# amp_test_4.net
KiCad netlist of a schematic drawn in EAGLE
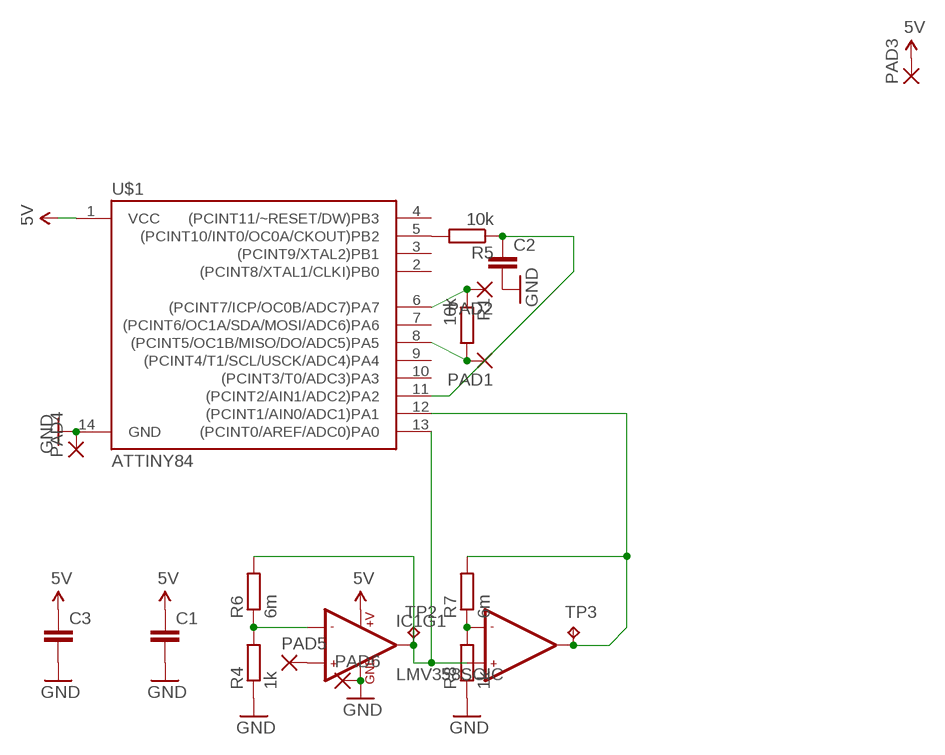
[diagram p0: schematic, sheet 1]

(export (version "E")
  (design (tool "Eeschema 10.0.6"))
  (components
    (comp (ref "C1")
      (value "C-EUC0603")
      (footprint "eagle-import:C0603")
      (libsource (lib "eagle-import") (part "C-EUC0603"))
    )
    (comp (ref "C2")
      (value "C-EUC0603")
      (footprint "eagle-import:C0603")
      (libsource (lib "eagle-import") (part "C-EUC0603"))
    )
    (comp (ref "C3")
      (value "C-EUC0603")
      (footprint "eagle-import:C0603")
      (libsource (lib "eagle-import") (part "C-EUC0603"))
    )
    (comp (ref "IC1")
      (value "LMV358SOIC")
      (footprint "eagle-import:SO08")
      (libsource (lib "eagle-import") (part "LMV358SOIC"))
    )
    (comp (ref "PAD1")
      (value "SMD5")
      (footprint "eagle-import:SMD2,54-5,08")
      (libsource (lib "eagle-import") (part "SMD5"))
    )
    (comp (ref "PAD2")
      (value "SMD5")
      (footprint "eagle-import:SMD2,54-5,08")
      (libsource (lib "eagle-import") (part "SMD5"))
    )
    (comp (ref "PAD3")
      (value "SMD5")
      (footprint "eagle-import:SMD2,54-5,08")
      (libsource (lib "eagle-import") (part "SMD5"))
    )
    (comp (ref "PAD4")
      (value "SMD5")
      (footprint "eagle-import:SMD2,54-5,08")
      (libsource (lib "eagle-import") (part "SMD5"))
    )
    (comp (ref "PAD5")
      (value "SMD5")
      (footprint "eagle-import:SMD2,54-5,08")
      (libsource (lib "eagle-import") (part "SMD5"))
    )
    (comp (ref "PAD6")
      (value "SMD5")
      (footprint "eagle-import:SMD2,54-5,08")
      (libsource (lib "eagle-import") (part "SMD5"))
    )
    (comp (ref "R1")
      (value "10k")
      (footprint "eagle-import:R0603")
      (libsource (lib "eagle-import") (part "R-EU_R0603"))
    )
    (comp (ref "R4")
      (value "1k")
      (footprint "eagle-import:R0603")
      (libsource (lib "eagle-import") (part "R-EU_R0603"))
    )
    (comp (ref "R5")
      (value "10k")
      (footprint "eagle-import:R0603")
      (libsource (lib "eagle-import") (part "R-EU_R0603"))
    )
    (comp (ref "R6")
      (value "6m")
      (footprint "eagle-import:R0603")
      (libsource (lib "eagle-import") (part "R-EU_R0603"))
    )
    (comp (ref "R7")
      (value "6m")
      (footprint "eagle-import:R0603")
      (libsource (lib "eagle-import") (part "R-EU_R0603"))
    )
    (comp (ref "R8")
      (value "1k")
      (footprint "eagle-import:R0603")
      (libsource (lib "eagle-import") (part "R-EU_R0603"))
    )
    (comp (ref "TP2")
      (value "TPTP20SQ")
      (footprint "eagle-import:TP20SQ")
      (libsource (lib "eagle-import") (part "TPTP20SQ"))
    )
    (comp (ref "TP3")
      (value "TPTP20SQ")
      (footprint "eagle-import:TP20SQ")
      (libsource (lib "eagle-import") (part "TPTP20SQ"))
    )
    (comp (ref "U$1")
      (value "ATTINY84")
      (footprint "eagle-import:SO14")
      (libsource (lib "eagle-import") (part "ATTINY84"))
    )
  )
  (nets
    (net (code "1") (name "5V") (class "Default")
      (node (ref "C1") (pin "1") (pinfunction "1_1") (pintype "passive"))
      (node (ref "C3") (pin "1") (pinfunction "1_1") (pintype "passive"))
      (node (ref "IC1") (pin "8") (pinfunction "+V_8") (pintype "power_in"))
      (node (ref "PAD3") (pin "1") (pinfunction "P_1") (pintype "passive"))
      (node (ref "U$1") (pin "1") (pinfunction "VCC_1") (pintype "bidirectional"))
    )
    (net (code "2") (name "GND") (class "Default")
      (node (ref "C1") (pin "2") (pinfunction "2_2") (pintype "passive"))
      (node (ref "C2") (pin "2") (pinfunction "2_2") (pintype "passive"))
      (node (ref "C3") (pin "2") (pinfunction "2_2") (pintype "passive"))
      (node (ref "IC1") (pin "4") (pinfunction "GND_4") (pintype "power_in"))
      (node (ref "PAD4") (pin "1") (pinfunction "P_1") (pintype "passive"))
      (node (ref "PAD6") (pin "1") (pinfunction "P_1") (pintype "passive"))
      (node (ref "R4") (pin "1") (pinfunction "1_1") (pintype "passive"))
      (node (ref "R8") (pin "1") (pinfunction "1_1") (pintype "passive"))
      (node (ref "U$1") (pin "14") (pinfunction "GND_14") (pintype "bidirectional"))
    )
    (net (code "3") (name "Net-(IC1A-+IN1)") (class "Default")
      (node (ref "IC1") (pin "3") (pinfunction "+IN1_3") (pintype "input"))
      (node (ref "PAD5") (pin "1") (pinfunction "P_1") (pintype "passive"))
    )
    (net (code "4") (name "Net-(IC1A--IN1)") (class "Default")
      (node (ref "IC1") (pin "2") (pinfunction "-IN1_2") (pintype "input"))
      (node (ref "R4") (pin "2") (pinfunction "2_2") (pintype "passive"))
      (node (ref "R6") (pin "1") (pinfunction "1_1") (pintype "passive"))
    )
    (net (code "5") (name "Net-(IC1A-OUT1)") (class "Default")
      (node (ref "IC1") (pin "1") (pinfunction "OUT1_1") (pintype "output"))
      (node (ref "IC1") (pin "5") (pinfunction "+IN2_5") (pintype "input"))
      (node (ref "R6") (pin "2") (pinfunction "2_2") (pintype "passive"))
      (node (ref "TP2") (pin "TP") (pinfunction "TP_TP") (pintype "input"))
      (node (ref "U$1") (pin "13") (pinfunction "(PCINT0/AREF/ADC0)PA0_13") (pintype "bidirectional"))
    )
    (net (code "6") (name "Net-(IC1B--IN2)") (class "Default")
      (node (ref "IC1") (pin "6") (pinfunction "-IN2_6") (pintype "input"))
      (node (ref "R7") (pin "1") (pinfunction "1_1") (pintype "passive"))
      (node (ref "R8") (pin "2") (pinfunction "2_2") (pintype "passive"))
    )
    (net (code "7") (name "Net-(IC1B-OUT2)") (class "Default")
      (node (ref "IC1") (pin "7") (pinfunction "OUT2_7") (pintype "output"))
      (node (ref "R7") (pin "2") (pinfunction "2_2") (pintype "passive"))
      (node (ref "TP3") (pin "TP") (pinfunction "TP_TP") (pintype "input"))
      (node (ref "U$1") (pin "12") (pinfunction "(PCINT1/AIN0/ADC1)PA1_12") (pintype "bidirectional"))
    )
    (net (code "8") (name "Net-(PAD1-P)") (class "Default")
      (node (ref "PAD1") (pin "1") (pinfunction "P_1") (pintype "passive"))
      (node (ref "R1") (pin "2") (pinfunction "2_2") (pintype "passive"))
      (node (ref "U$1") (pin "8") (pinfunction "(PCINT5/OC1B/MISO/DO/ADC5)PA5_8") (pintype "bidirectional"))
    )
    (net (code "9") (name "Net-(PAD2-P)") (class "Default")
      (node (ref "PAD2") (pin "1") (pinfunction "P_1") (pintype "passive"))
      (node (ref "R1") (pin "1") (pinfunction "1_1") (pintype "passive"))
      (node (ref "U$1") (pin "6") (pinfunction "(PCINT7/ICP/OC0B/ADC7)PA7_6") (pintype "bidirectional"))
    )
    (net (code "10") (name "Net-(U$1-(PCINT2{slash}AIN1{slash}ADC2)PA2)") (class "Default")
      (node (ref "C2") (pin "1") (pinfunction "1_1") (pintype "passive"))
      (node (ref "R5") (pin "1") (pinfunction "1_1") (pintype "passive"))
      (node (ref "U$1") (pin "11") (pinfunction "(PCINT2/AIN1/ADC2)PA2_11") (pintype "bidirectional"))
    )
    (net (code "11") (name "Net-(U$1-(PCINT10{slash}INT0{slash}OC0A{slash}CKOUT)PB2)") (class "Default")
      (node (ref "R5") (pin "2") (pinfunction "2_2") (pintype "passive"))
      (node (ref "U$1") (pin "5") (pinfunction "(PCINT10/INT0/OC0A/CKOUT)PB2_5") (pintype "bidirectional"))
    )
    (net (code "12") (name "unconnected-(U$1-(PCINT3{slash}T0{slash}ADC3)PA3-Pad10)") (class "Default")
      (node (ref "U$1") (pin "10") (pinfunction "(PCINT3/T0/ADC3)PA3_10") (pintype "bidirectional"))
    )
    (net (code "13") (name "unconnected-(U$1-(PCINT4{slash}T1{slash}SCL{slash}USCK{slash}ADC4)PA4-Pad9)") (class "Default")
      (node (ref "U$1") (pin "9") (pinfunction "(PCINT4/T1/SCL/USCK/ADC4)PA4_9") (pintype "bidirectional"))
    )
    (net (code "14") (name "unconnected-(U$1-(PCINT6{slash}OC1A{slash}SDA{slash}MOSI{slash}ADC6)PA6-Pad7)") (class "Default")
      (node (ref "U$1") (pin "7") (pinfunction "(PCINT6/OC1A/SDA/MOSI/ADC6)PA6_7") (pintype "bidirectional"))
    )
    (net (code "15") (name "unconnected-(U$1-(PCINT8{slash}XTAL1{slash}CLKI)PB0-Pad2)") (class "Default")
      (node (ref "U$1") (pin "2") (pinfunction "(PCINT8/XTAL1/CLKI)PB0_2") (pintype "bidirectional"))
    )
    (net (code "16") (name "unconnected-(U$1-(PCINT9{slash}XTAL2)PB1-Pad3)") (class "Default")
      (node (ref "U$1") (pin "3") (pinfunction "(PCINT9/XTAL2)PB1_3") (pintype "bidirectional"))
    )
    (net (code "17") (name "unconnected-(U$1-(PCINT11{slash}~{RESET{slash}DW})PB3-Pad4)") (class "Default")
      (node (ref "U$1") (pin "4") (pinfunction "(PCINT11/~{RESET/DW})PB3_4") (pintype "bidirectional"))
    )
  )
)
